# iBookG3Clamshell_T4p0.net
KiCad netlist of a schematic drawn in EAGLE
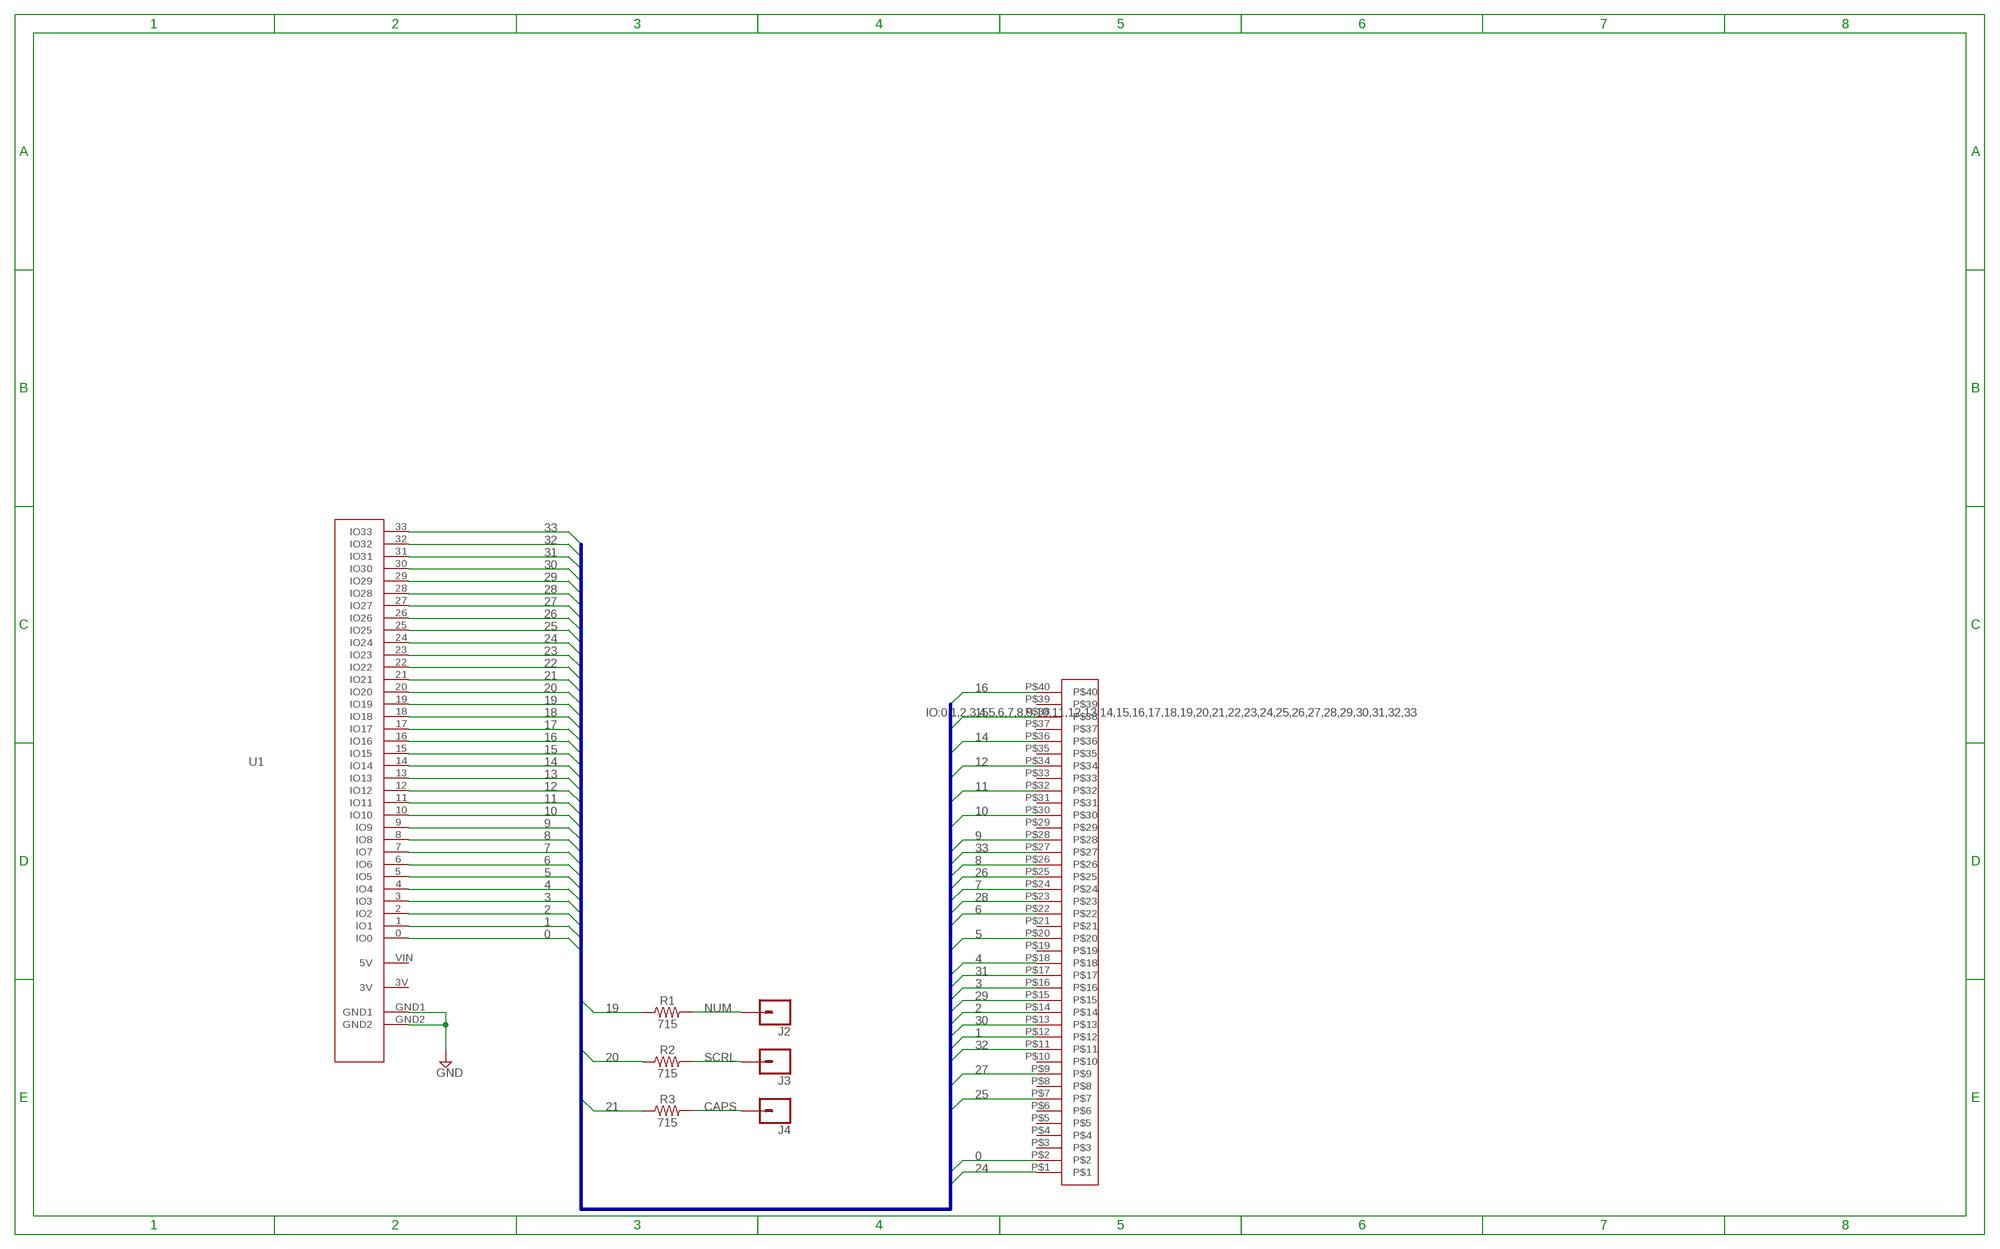
[diagram p0: schematic, sheet 1]

(export (version "E")
  (design (tool "Eeschema 10.0.6"))
  (components
    (comp (ref "J1")
      (value "HDR127MET40FGVSMDR")
      (footprint "eagle-import:HDR127MET40FGVSMDR")
      (libsource (lib "eagle-import") (part "HDR127MET40FGVSMDR"))
    )
    (comp (ref "J2")
      (value "CONN_01PTH_NO_SILK_YES_STOP")
      (footprint "eagle-import:1X01_NO_SILK")
      (libsource (lib "eagle-import") (part "CONN_01PTH_NO_SILK_YES_STOP"))
    )
    (comp (ref "J3")
      (value "CONN_01PTH_NO_SILK_YES_STOP")
      (footprint "eagle-import:1X01_NO_SILK")
      (libsource (lib "eagle-import") (part "CONN_01PTH_NO_SILK_YES_STOP"))
    )
    (comp (ref "J4")
      (value "CONN_01PTH_NO_SILK_YES_STOP")
      (footprint "eagle-import:1X01_NO_SILK")
      (libsource (lib "eagle-import") (part "CONN_01PTH_NO_SILK_YES_STOP"))
    )
    (comp (ref "R1")
      (value "715")
      (footprint "eagle-import:0603")
      (libsource (lib "eagle-import") (part "715OHM-0603-1/10W-1%"))
    )
    (comp (ref "R2")
      (value "715")
      (footprint "eagle-import:0603")
      (libsource (lib "eagle-import") (part "715OHM-0603-1/10W-1%"))
    )
    (comp (ref "R3")
      (value "715")
      (footprint "eagle-import:0603")
      (libsource (lib "eagle-import") (part "715OHM-0603-1/10W-1%"))
    )
    (comp (ref "U1")
      (value "TEENSY4P0_CUTOUT")
      (footprint "eagle-import:TEENSY4P0_CUTOUT")
      (libsource (lib "eagle-import") (part "TEENSY4P0_CUTOUT"))
    )
  )
  (nets
    (net (code "2") (name "/0") (class "Default")
      (node (ref "J1") (pin "P$2") (pinfunction "P$2_P$2") (pintype "bidirectional"))
      (node (ref "U1") (pin "0") (pinfunction "IO0_0") (pintype "bidirectional"))
    )
    (net (code "3") (name "/1") (class "Default")
      (node (ref "J1") (pin "P$12") (pinfunction "P$12_P$12") (pintype "bidirectional"))
      (node (ref "U1") (pin "1") (pinfunction "IO1_1") (pintype "bidirectional"))
    )
    (net (code "4") (name "/2") (class "Default")
      (node (ref "J1") (pin "P$14") (pinfunction "P$14_P$14") (pintype "bidirectional"))
      (node (ref "U1") (pin "2") (pinfunction "IO2_2") (pintype "bidirectional"))
    )
    (net (code "5") (name "/3") (class "Default")
      (node (ref "J1") (pin "P$16") (pinfunction "P$16_P$16") (pintype "bidirectional"))
      (node (ref "U1") (pin "3") (pinfunction "IO3_3") (pintype "bidirectional"))
    )
    (net (code "6") (name "/4") (class "Default")
      (node (ref "J1") (pin "P$18") (pinfunction "P$18_P$18") (pintype "bidirectional"))
      (node (ref "U1") (pin "4") (pinfunction "IO4_4") (pintype "bidirectional"))
    )
    (net (code "7") (name "/5") (class "Default")
      (node (ref "J1") (pin "P$20") (pinfunction "P$20_P$20") (pintype "bidirectional"))
      (node (ref "U1") (pin "5") (pinfunction "IO5_5") (pintype "bidirectional"))
    )
    (net (code "8") (name "/6") (class "Default")
      (node (ref "J1") (pin "P$22") (pinfunction "P$22_P$22") (pintype "bidirectional"))
      (node (ref "U1") (pin "6") (pinfunction "IO6_6") (pintype "bidirectional"))
    )
    (net (code "9") (name "/7") (class "Default")
      (node (ref "J1") (pin "P$24") (pinfunction "P$24_P$24") (pintype "bidirectional"))
      (node (ref "U1") (pin "7") (pinfunction "IO7_7") (pintype "bidirectional"))
    )
    (net (code "10") (name "/8") (class "Default")
      (node (ref "J1") (pin "P$26") (pinfunction "P$26_P$26") (pintype "bidirectional"))
      (node (ref "U1") (pin "8") (pinfunction "IO8_8") (pintype "bidirectional"))
    )
    (net (code "11") (name "/9") (class "Default")
      (node (ref "J1") (pin "P$28") (pinfunction "P$28_P$28") (pintype "bidirectional"))
      (node (ref "U1") (pin "9") (pinfunction "IO9_9") (pintype "bidirectional"))
    )
    (net (code "12") (name "/10") (class "Default")
      (node (ref "J1") (pin "P$30") (pinfunction "P$30_P$30") (pintype "bidirectional"))
      (node (ref "U1") (pin "10") (pinfunction "IO10_10") (pintype "bidirectional"))
    )
    (net (code "13") (name "/11") (class "Default")
      (node (ref "J1") (pin "P$32") (pinfunction "P$32_P$32") (pintype "bidirectional"))
      (node (ref "U1") (pin "11") (pinfunction "IO11_11") (pintype "bidirectional"))
    )
    (net (code "14") (name "/12") (class "Default")
      (node (ref "J1") (pin "P$34") (pinfunction "P$34_P$34") (pintype "bidirectional"))
      (node (ref "U1") (pin "12") (pinfunction "IO12_12") (pintype "bidirectional"))
    )
    (net (code "15") (name "/13") (class "Default")
      (node (ref "U1") (pin "13") (pinfunction "IO13_13") (pintype "bidirectional"))
    )
    (net (code "16") (name "/14") (class "Default")
      (node (ref "J1") (pin "P$36") (pinfunction "P$36_P$36") (pintype "bidirectional"))
      (node (ref "U1") (pin "14") (pinfunction "IO14_14") (pintype "bidirectional"))
    )
    (net (code "17") (name "/15") (class "Default")
      (node (ref "J1") (pin "P$38") (pinfunction "P$38_P$38") (pintype "bidirectional"))
      (node (ref "U1") (pin "15") (pinfunction "IO15_15") (pintype "bidirectional"))
    )
    (net (code "18") (name "/16") (class "Default")
      (node (ref "J1") (pin "P$40") (pinfunction "P$40_P$40") (pintype "bidirectional"))
      (node (ref "U1") (pin "16") (pinfunction "IO16_16") (pintype "bidirectional"))
    )
    (net (code "19") (name "/17") (class "Default")
      (node (ref "U1") (pin "17") (pinfunction "IO17_17") (pintype "bidirectional"))
    )
    (net (code "20") (name "/18") (class "Default")
      (node (ref "U1") (pin "18") (pinfunction "IO18_18") (pintype "bidirectional"))
    )
    (net (code "21") (name "/19") (class "Default")
      (node (ref "R1") (pin "1") (pinfunction "1_1") (pintype "passive"))
      (node (ref "U1") (pin "19") (pinfunction "IO19_19") (pintype "bidirectional"))
    )
    (net (code "22") (name "/20") (class "Default")
      (node (ref "R2") (pin "1") (pinfunction "1_1") (pintype "passive"))
      (node (ref "U1") (pin "20") (pinfunction "IO20_20") (pintype "bidirectional"))
    )
    (net (code "23") (name "/21") (class "Default")
      (node (ref "R3") (pin "1") (pinfunction "1_1") (pintype "passive"))
      (node (ref "U1") (pin "21") (pinfunction "IO21_21") (pintype "bidirectional"))
    )
    (net (code "24") (name "/22") (class "Default")
      (node (ref "U1") (pin "22") (pinfunction "IO22_22") (pintype "bidirectional"))
    )
    (net (code "25") (name "/23") (class "Default")
      (node (ref "U1") (pin "23") (pinfunction "IO23_23") (pintype "bidirectional"))
    )
    (net (code "26") (name "/24") (class "Default")
      (node (ref "J1") (pin "P$1") (pinfunction "P$1_P$1") (pintype "bidirectional"))
      (node (ref "U1") (pin "24") (pinfunction "IO24_24") (pintype "bidirectional"))
    )
    (net (code "27") (name "/25") (class "Default")
      (node (ref "J1") (pin "P$7") (pinfunction "P$7_P$7") (pintype "bidirectional"))
      (node (ref "U1") (pin "25") (pinfunction "IO25_25") (pintype "bidirectional"))
    )
    (net (code "28") (name "/26") (class "Default")
      (node (ref "J1") (pin "P$25") (pinfunction "P$25_P$25") (pintype "bidirectional"))
      (node (ref "U1") (pin "26") (pinfunction "IO26_26") (pintype "bidirectional"))
    )
    (net (code "29") (name "/27") (class "Default")
      (node (ref "J1") (pin "P$9") (pinfunction "P$9_P$9") (pintype "bidirectional"))
      (node (ref "U1") (pin "27") (pinfunction "IO27_27") (pintype "bidirectional"))
    )
    (net (code "30") (name "/28") (class "Default")
      (node (ref "J1") (pin "P$23") (pinfunction "P$23_P$23") (pintype "bidirectional"))
      (node (ref "U1") (pin "28") (pinfunction "IO28_28") (pintype "bidirectional"))
    )
    (net (code "31") (name "/29") (class "Default")
      (node (ref "J1") (pin "P$15") (pinfunction "P$15_P$15") (pintype "bidirectional"))
      (node (ref "U1") (pin "29") (pinfunction "IO29_29") (pintype "bidirectional"))
    )
    (net (code "32") (name "/30") (class "Default")
      (node (ref "J1") (pin "P$13") (pinfunction "P$13_P$13") (pintype "bidirectional"))
      (node (ref "U1") (pin "30") (pinfunction "IO30_30") (pintype "bidirectional"))
    )
    (net (code "33") (name "/31") (class "Default")
      (node (ref "J1") (pin "P$17") (pinfunction "P$17_P$17") (pintype "bidirectional"))
      (node (ref "U1") (pin "31") (pinfunction "IO31_31") (pintype "bidirectional"))
    )
    (net (code "34") (name "/32") (class "Default")
      (node (ref "J1") (pin "P$11") (pinfunction "P$11_P$11") (pintype "bidirectional"))
      (node (ref "U1") (pin "32") (pinfunction "IO32_32") (pintype "bidirectional"))
    )
    (net (code "35") (name "/33") (class "Default")
      (node (ref "J1") (pin "P$27") (pinfunction "P$27_P$27") (pintype "bidirectional"))
      (node (ref "U1") (pin "33") (pinfunction "IO33_33") (pintype "bidirectional"))
    )
    (net (code "36") (name "/CAPS") (class "Default")
      (node (ref "J4") (pin "1") (pinfunction "1_1") (pintype "passive"))
      (node (ref "R3") (pin "2") (pinfunction "2_2") (pintype "passive"))
    )
    (net (code "37") (name "/NUM") (class "Default")
      (node (ref "J2") (pin "1") (pinfunction "1_1") (pintype "passive"))
      (node (ref "R1") (pin "2") (pinfunction "2_2") (pintype "passive"))
    )
    (net (code "38") (name "/SCRL") (class "Default")
      (node (ref "J3") (pin "1") (pinfunction "1_1") (pintype "passive"))
      (node (ref "R2") (pin "2") (pinfunction "2_2") (pintype "passive"))
    )
    (net (code "40") (name "GND") (class "Default")
      (node (ref "U1") (pin "GND1") (pinfunction "GND1_GND1") (pintype "bidirectional"))
      (node (ref "U1") (pin "GND2") (pinfunction "GND2_GND2") (pintype "bidirectional"))
    )
    (net (code "41") (name "unconnected-(J1-PadP$3)") (class "Default")
      (node (ref "J1") (pin "P$3") (pinfunction "P$3_P$3") (pintype "bidirectional"))
    )
    (net (code "42") (name "unconnected-(J1-PadP$4)") (class "Default")
      (node (ref "J1") (pin "P$4") (pinfunction "P$4_P$4") (pintype "bidirectional"))
    )
    (net (code "43") (name "unconnected-(J1-PadP$5)") (class "Default")
      (node (ref "J1") (pin "P$5") (pinfunction "P$5_P$5") (pintype "bidirectional"))
    )
    (net (code "44") (name "unconnected-(J1-PadP$6)") (class "Default")
      (node (ref "J1") (pin "P$6") (pinfunction "P$6_P$6") (pintype "bidirectional"))
    )
    (net (code "45") (name "unconnected-(J1-PadP$8)") (class "Default")
      (node (ref "J1") (pin "P$8") (pinfunction "P$8_P$8") (pintype "bidirectional"))
    )
    (net (code "46") (name "unconnected-(J1-PadP$10)") (class "Default")
      (node (ref "J1") (pin "P$10") (pinfunction "P$10_P$10") (pintype "bidirectional"))
    )
    (net (code "47") (name "unconnected-(J1-PadP$19)") (class "Default")
      (node (ref "J1") (pin "P$19") (pinfunction "P$19_P$19") (pintype "bidirectional"))
    )
    (net (code "48") (name "unconnected-(J1-PadP$21)") (class "Default")
      (node (ref "J1") (pin "P$21") (pinfunction "P$21_P$21") (pintype "bidirectional"))
    )
    (net (code "49") (name "unconnected-(J1-PadP$29)") (class "Default")
      (node (ref "J1") (pin "P$29") (pinfunction "P$29_P$29") (pintype "bidirectional"))
    )
    (net (code "50") (name "unconnected-(J1-PadP$31)") (class "Default")
      (node (ref "J1") (pin "P$31") (pinfunction "P$31_P$31") (pintype "bidirectional"))
    )
    (net (code "51") (name "unconnected-(J1-PadP$33)") (class "Default")
      (node (ref "J1") (pin "P$33") (pinfunction "P$33_P$33") (pintype "bidirectional"))
    )
    (net (code "52") (name "unconnected-(J1-PadP$35)") (class "Default")
      (node (ref "J1") (pin "P$35") (pinfunction "P$35_P$35") (pintype "bidirectional"))
    )
    (net (code "53") (name "unconnected-(J1-PadP$37)") (class "Default")
      (node (ref "J1") (pin "P$37") (pinfunction "P$37_P$37") (pintype "bidirectional"))
    )
    (net (code "54") (name "unconnected-(J1-PadP$39)") (class "Default")
      (node (ref "J1") (pin "P$39") (pinfunction "P$39_P$39") (pintype "bidirectional"))
    )
    (net (code "55") (name "unconnected-(U1-5V-PadVIN)") (class "Default")
      (node (ref "U1") (pin "VIN") (pinfunction "5V_VIN") (pintype "bidirectional"))
    )
    (net (code "56") (name "unconnected-(U1-Pad3V)") (class "Default")
      (node (ref "U1") (pin "3V") (pinfunction "3V_3V") (pintype "bidirectional"))
    )
  )
)
